# Gpio_RTC.net
KiCad netlist of a schematic drawn in Altium Designer
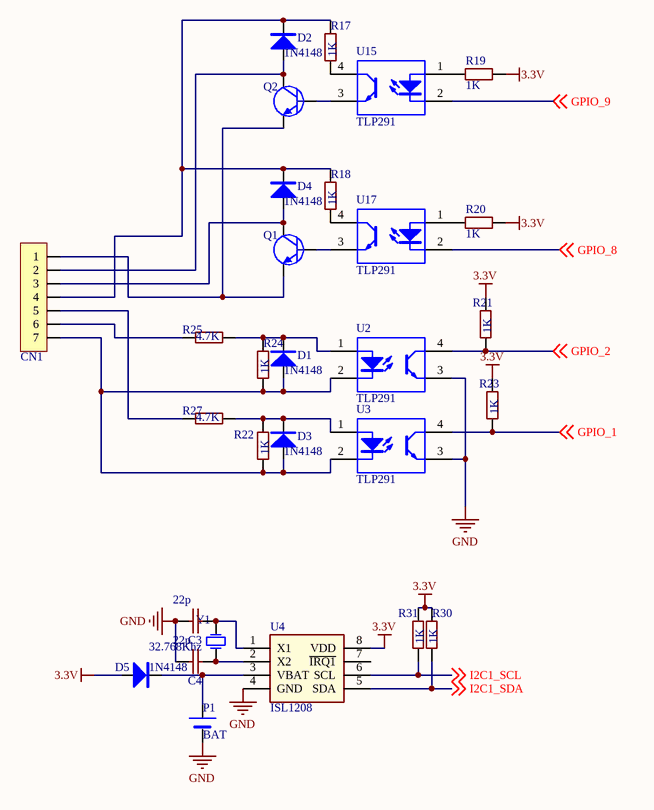
[diagram p0: Gpio_RTC.SchDoc]

(export (version "E")
  (design (tool "Eeschema 10.0.6"))
  (components
    (comp (ref "C3")
      (value "22p")
      (footprint "0805SMD_Cap")
      (description "贴片电容")
      (libsource (lib "ST_GND_Sch") (part "SMD_Cap"))
    )
    (comp (ref "C4")
      (value "22p")
      (footprint "0805SMD_Cap")
      (description "贴片电容")
      (libsource (lib "ST_GND_Sch") (part "SMD_Cap"))
    )
    (comp (ref "CN1")
      (value "CON7")
      (footprint "WJ15EDGRM-3.81-7P")
      (description "连接器")
      (libsource (lib "ST_GND_Sch") (part "CON7"))
    )
    (comp (ref "D1")
      (value "1N4148")
      (footprint "二极管SOD-123")
      (description "二极管")
      (libsource (lib "ST_GND_Sch") (part "DIODE"))
    )
    (comp (ref "D2")
      (value "1N4148")
      (footprint "二极管SOD-123")
      (description "二极管")
      (libsource (lib "ST_GND_Sch") (part "DIODE"))
    )
    (comp (ref "D3")
      (value "1N4148")
      (footprint "二极管SOD-123")
      (description "二极管")
      (libsource (lib "ST_GND_Sch") (part "DIODE"))
    )
    (comp (ref "D4")
      (value "1N4148")
      (footprint "二极管SOD-123")
      (description "二极管")
      (libsource (lib "ST_GND_Sch") (part "DIODE"))
    )
    (comp (ref "D5")
      (value "1N4148")
      (footprint "二极管SOD-123")
      (description "二极管")
      (libsource (lib "ST_GND_Sch") (part "DIODE"))
    )
    (comp (ref "P1") (value "BAT") (footprint "CR1220") (libsource (lib "ST_GND_Sch") (part "BAT")))
    (comp (ref "Q1")
      (value "1318")
      (footprint "SOT-23")
      (description "三极管")
      (fields (field (name "PUBLISHER") "Altium Limited"))
      (libsource (lib "ST_GND_Sch") (part "三极管"))
    )
    (comp (ref "Q2")
      (value "1318")
      (footprint "SOT-23")
      (description "三极管")
      (fields (field (name "PUBLISHER") "Altium Limited"))
      (libsource (lib "ST_GND_Sch") (part "三极管"))
    )
    (comp (ref "R17")
      (value "1K")
      (footprint "0805_SMD_R")
      (description "贴片电阻")
      (libsource (lib "ST_GND_Sch") (part "SMD_0805"))
    )
    (comp (ref "R18")
      (value "1K")
      (footprint "0805_SMD_R")
      (description "贴片电阻")
      (libsource (lib "ST_GND_Sch") (part "SMD_0805"))
    )
    (comp (ref "R19")
      (value "1K")
      (footprint "0805_SMD_R")
      (description "贴片电阻")
      (libsource (lib "") (part "SMD_0805_1"))
    )
    (comp (ref "R20")
      (value "1K")
      (footprint "0805_SMD_R")
      (description "贴片电阻")
      (libsource (lib "") (part "SMD_0805_1"))
    )
    (comp (ref "R21")
      (value "1K")
      (footprint "0805_SMD_R")
      (description "贴片电阻")
      (libsource (lib "ST_GND_Sch") (part "SMD_0805"))
    )
    (comp (ref "R22")
      (value "1K")
      (footprint "0805_SMD_R")
      (description "贴片电阻")
      (libsource (lib "ST_GND_Sch") (part "SMD_0805"))
    )
    (comp (ref "R23")
      (value "1K")
      (footprint "0805_SMD_R")
      (description "贴片电阻")
      (libsource (lib "ST_GND_Sch") (part "SMD_0805"))
    )
    (comp (ref "R24")
      (value "1K")
      (footprint "0805_SMD_R")
      (description "贴片电阻")
      (libsource (lib "ST_GND_Sch") (part "SMD_0805"))
    )
    (comp (ref "R25")
      (value "4.7K")
      (footprint "0805_SMD_R")
      (description "贴片电阻")
      (libsource (lib "") (part "SMD_0805_2"))
    )
    (comp (ref "R27")
      (value "4.7K")
      (footprint "0805_SMD_R")
      (description "贴片电阻")
      (libsource (lib "") (part "SMD_0805_2"))
    )
    (comp (ref "R30")
      (value "1K")
      (footprint "0805_SMD_R")
      (description "贴片电阻")
      (libsource (lib "") (part "SMD_0805_1"))
    )
    (comp (ref "R31")
      (value "1K")
      (footprint "0805_SMD_R")
      (description "贴片电阻")
      (libsource (lib "") (part "SMD_0805_1"))
    )
    (comp (ref "U2") (value "TLP291") (footprint "sop-4") (libsource (lib "ST_GND_Sch") (part "TLP291")))
    (comp (ref "U3") (value "TLP291") (footprint "sop-4") (libsource (lib "ST_GND_Sch") (part "TLP291")))
    (comp (ref "U4")
      (value "ISL1208")
      (footprint "运放SO8")
      (description "时钟芯片")
      (libsource (lib "ST_GND_Sch") (part "ISL1208"))
    )
    (comp (ref "U15") (value "TLP291") (footprint "sop-4") (libsource (lib "ST_GND_Sch") (part "TLP291")))
    (comp (ref "U17") (value "TLP291") (footprint "sop-4") (libsource (lib "ST_GND_Sch") (part "TLP291")))
    (comp (ref "Y1")
      (value "32.768Khz")
      (footprint "XTAL_0503_2Pin")
      (description "无源晶振贴装")
      (fields (field (name "PUBLISHER") "Altium Limited"))
      (libsource (lib "ST_GND_Sch") (part "XTAL"))
    )
  )
  (nets
    (net (code "1") (name "3.3V") (class "Default")
      (node (ref "D5") (pin "A") (pintype "passive"))
      (node (ref "R19") (pin "1") (pinfunction "1_1") (pintype "passive"))
      (node (ref "R20") (pin "1") (pinfunction "1_1") (pintype "passive"))
      (node (ref "R21") (pin "2") (pinfunction "2_2") (pintype "passive"))
      (node (ref "R23") (pin "2") (pinfunction "2_2") (pintype "passive"))
      (node (ref "R30") (pin "1") (pinfunction "1_1") (pintype "passive"))
      (node (ref "R31") (pin "1") (pinfunction "1_1") (pintype "passive"))
      (node (ref "U4") (pin "8") (pinfunction "VDD_8") (pintype "passive"))
    )
    (net (code "2") (name "GND") (class "Default")
      (node (ref "C3") (pin "1") (pintype "passive"))
      (node (ref "C4") (pin "1") (pintype "passive"))
      (node (ref "P1") (pin "2") (pinfunction "-_2") (pintype "passive"))
      (node (ref "U2") (pin "3") (pinfunction "3_3") (pintype "passive"))
      (node (ref "U3") (pin "3") (pinfunction "3_3") (pintype "passive"))
      (node (ref "U4") (pin "4") (pinfunction "GND_4") (pintype "passive"))
    )
    (net (code "3") (name "GPIO_1") (class "Default")
      (node (ref "R23") (pin "1") (pinfunction "1_1") (pintype "passive"))
      (node (ref "U3") (pin "4") (pinfunction "4_4") (pintype "passive"))
    )
    (net (code "4") (name "GPIO_2") (class "Default")
      (node (ref "R21") (pin "1") (pinfunction "1_1") (pintype "passive"))
      (node (ref "U2") (pin "4") (pinfunction "4_4") (pintype "passive"))
    )
    (net (code "5") (name "GPIO_8") (class "Default")
      (node (ref "U17") (pin "2") (pinfunction "2_2") (pintype "passive"))
    )
    (net (code "6") (name "GPIO_9") (class "Default")
      (node (ref "U15") (pin "2") (pinfunction "2_2") (pintype "passive"))
    )
    (net (code "7") (name "I2C1_SCL") (class "Default")
      (node (ref "R31") (pin "2") (pinfunction "2_2") (pintype "passive"))
      (node (ref "U4") (pin "6") (pinfunction "SCL_6") (pintype "passive"))
    )
    (net (code "8") (name "I2C1_SDA") (class "Default")
      (node (ref "R30") (pin "2") (pinfunction "2_2") (pintype "passive"))
      (node (ref "U4") (pin "5") (pinfunction "SDA_5") (pintype "passive"))
    )
    (net (code "9") (name "Net-(CN1-Pad4)") (class "Default")
      (node (ref "CN1") (pin "4") (pinfunction "4_4") (pintype "passive"))
      (node (ref "D2") (pin "K") (pintype "passive"))
      (node (ref "D4") (pin "K") (pintype "passive"))
      (node (ref "R17") (pin "2") (pinfunction "2_2") (pintype "passive"))
      (node (ref "R18") (pin "2") (pinfunction "2_2") (pintype "passive"))
    )
    (net (code "10") (name "Net-(CN1-Pad5)") (class "Default")
      (node (ref "CN1") (pin "5") (pinfunction "5_5") (pintype "passive"))
      (node (ref "R27") (pin "1") (pinfunction "1_1") (pintype "passive"))
    )
    (net (code "11") (name "Net-(CN1-Pad6)") (class "Default")
      (node (ref "CN1") (pin "6") (pinfunction "6_6") (pintype "passive"))
      (node (ref "R25") (pin "1") (pinfunction "1_1") (pintype "passive"))
    )
    (net (code "12") (name "Net-(CN1-Pad7)") (class "Default")
      (node (ref "CN1") (pin "7") (pinfunction "7_7") (pintype "passive"))
      (node (ref "D1") (pin "A") (pintype "passive"))
      (node (ref "D3") (pin "A") (pintype "passive"))
      (node (ref "R22") (pin "1") (pinfunction "1_1") (pintype "passive"))
      (node (ref "R24") (pin "1") (pinfunction "1_1") (pintype "passive"))
      (node (ref "U2") (pin "2") (pinfunction "2_2") (pintype "passive"))
      (node (ref "U3") (pin "2") (pinfunction "2_2") (pintype "passive"))
    )
    (net (code "13") (name "Net-(D1-PadK)") (class "Default")
      (node (ref "D1") (pin "K") (pintype "passive"))
      (node (ref "R24") (pin "2") (pinfunction "2_2") (pintype "passive"))
      (node (ref "R25") (pin "2") (pinfunction "2_2") (pintype "passive"))
      (node (ref "U2") (pin "1") (pinfunction "1_1") (pintype "passive"))
    )
    (net (code "14") (name "Net-(D3-PadK)") (class "Default")
      (node (ref "D3") (pin "K") (pintype "passive"))
      (node (ref "R22") (pin "2") (pinfunction "2_2") (pintype "passive"))
      (node (ref "R27") (pin "2") (pinfunction "2_2") (pintype "passive"))
      (node (ref "U3") (pin "1") (pinfunction "1_1") (pintype "passive"))
    )
    (net (code "15") (name "Net-(P1-+)") (class "Default")
      (node (ref "D5") (pin "K") (pintype "passive"))
      (node (ref "P1") (pin "1") (pinfunction "+_1") (pintype "passive"))
      (node (ref "U4") (pin "3") (pinfunction "VBAT_3") (pintype "passive"))
    )
    (net (code "16") (name "Net-(Q1-B)") (class "Default")
      (node (ref "Q1") (pin "1") (pinfunction "B_1") (pintype "passive"))
      (node (ref "U17") (pin "3") (pinfunction "3_3") (pintype "passive"))
    )
    (net (code "17") (name "Net-(Q1-C)") (class "Default")
      (node (ref "CN1") (pin "3") (pinfunction "3_3") (pintype "passive"))
      (node (ref "D4") (pin "A") (pintype "passive"))
      (node (ref "Q1") (pin "3") (pinfunction "C_3") (pintype "passive"))
    )
    (net (code "18") (name "Net-(Q1-E)") (class "Default")
      (node (ref "CN1") (pin "1") (pinfunction "1_1") (pintype "passive"))
      (node (ref "Q1") (pin "2") (pinfunction "E_2") (pintype "passive"))
      (node (ref "Q2") (pin "2") (pinfunction "E_2") (pintype "passive"))
    )
    (net (code "19") (name "Net-(Q2-B)") (class "Default")
      (node (ref "Q2") (pin "1") (pinfunction "B_1") (pintype "passive"))
      (node (ref "U15") (pin "3") (pinfunction "3_3") (pintype "passive"))
    )
    (net (code "20") (name "Net-(Q2-C)") (class "Default")
      (node (ref "CN1") (pin "2") (pinfunction "2_2") (pintype "passive"))
      (node (ref "D2") (pin "A") (pintype "passive"))
      (node (ref "Q2") (pin "3") (pinfunction "C_3") (pintype "passive"))
    )
    (net (code "21") (name "Net-(R17-Pad1)") (class "Default")
      (node (ref "R17") (pin "1") (pinfunction "1_1") (pintype "passive"))
      (node (ref "U15") (pin "4") (pinfunction "4_4") (pintype "passive"))
    )
    (net (code "22") (name "Net-(R18-Pad1)") (class "Default")
      (node (ref "R18") (pin "1") (pinfunction "1_1") (pintype "passive"))
      (node (ref "U17") (pin "4") (pinfunction "4_4") (pintype "passive"))
    )
    (net (code "23") (name "Net-(R19-Pad2)") (class "Default")
      (node (ref "R19") (pin "2") (pinfunction "2_2") (pintype "passive"))
      (node (ref "U15") (pin "1") (pinfunction "1_1") (pintype "passive"))
    )
    (net (code "24") (name "Net-(R20-Pad2)") (class "Default")
      (node (ref "R20") (pin "2") (pinfunction "2_2") (pintype "passive"))
      (node (ref "U17") (pin "1") (pinfunction "1_1") (pintype "passive"))
    )
    (net (code "25") (name "Net-(U4-X1)") (class "Default")
      (node (ref "C3") (pin "2") (pintype "passive"))
      (node (ref "U4") (pin "1") (pinfunction "X1_1") (pintype "passive"))
      (node (ref "Y1") (pin "2") (pinfunction "OSC2_2") (pintype "passive"))
    )
    (net (code "26") (name "Net-(U4-X2)") (class "Default")
      (node (ref "C4") (pin "2") (pintype "passive"))
      (node (ref "U4") (pin "2") (pinfunction "X2_2") (pintype "passive"))
      (node (ref "Y1") (pin "1") (pinfunction "OSC1_1") (pintype "passive"))
    )
    (net (code "27") (name "unconnected-(U4-~{IRQ1}-Pad7)") (class "Default")
      (node (ref "U4") (pin "7") (pinfunction "~{IRQ1}_7") (pintype "passive"))
    )
  )
)
